# NNP-DWG-165-001-000_BP2_Analog-Digital_P.net
KiCad netlist of a schematic drawn in Altium Designer
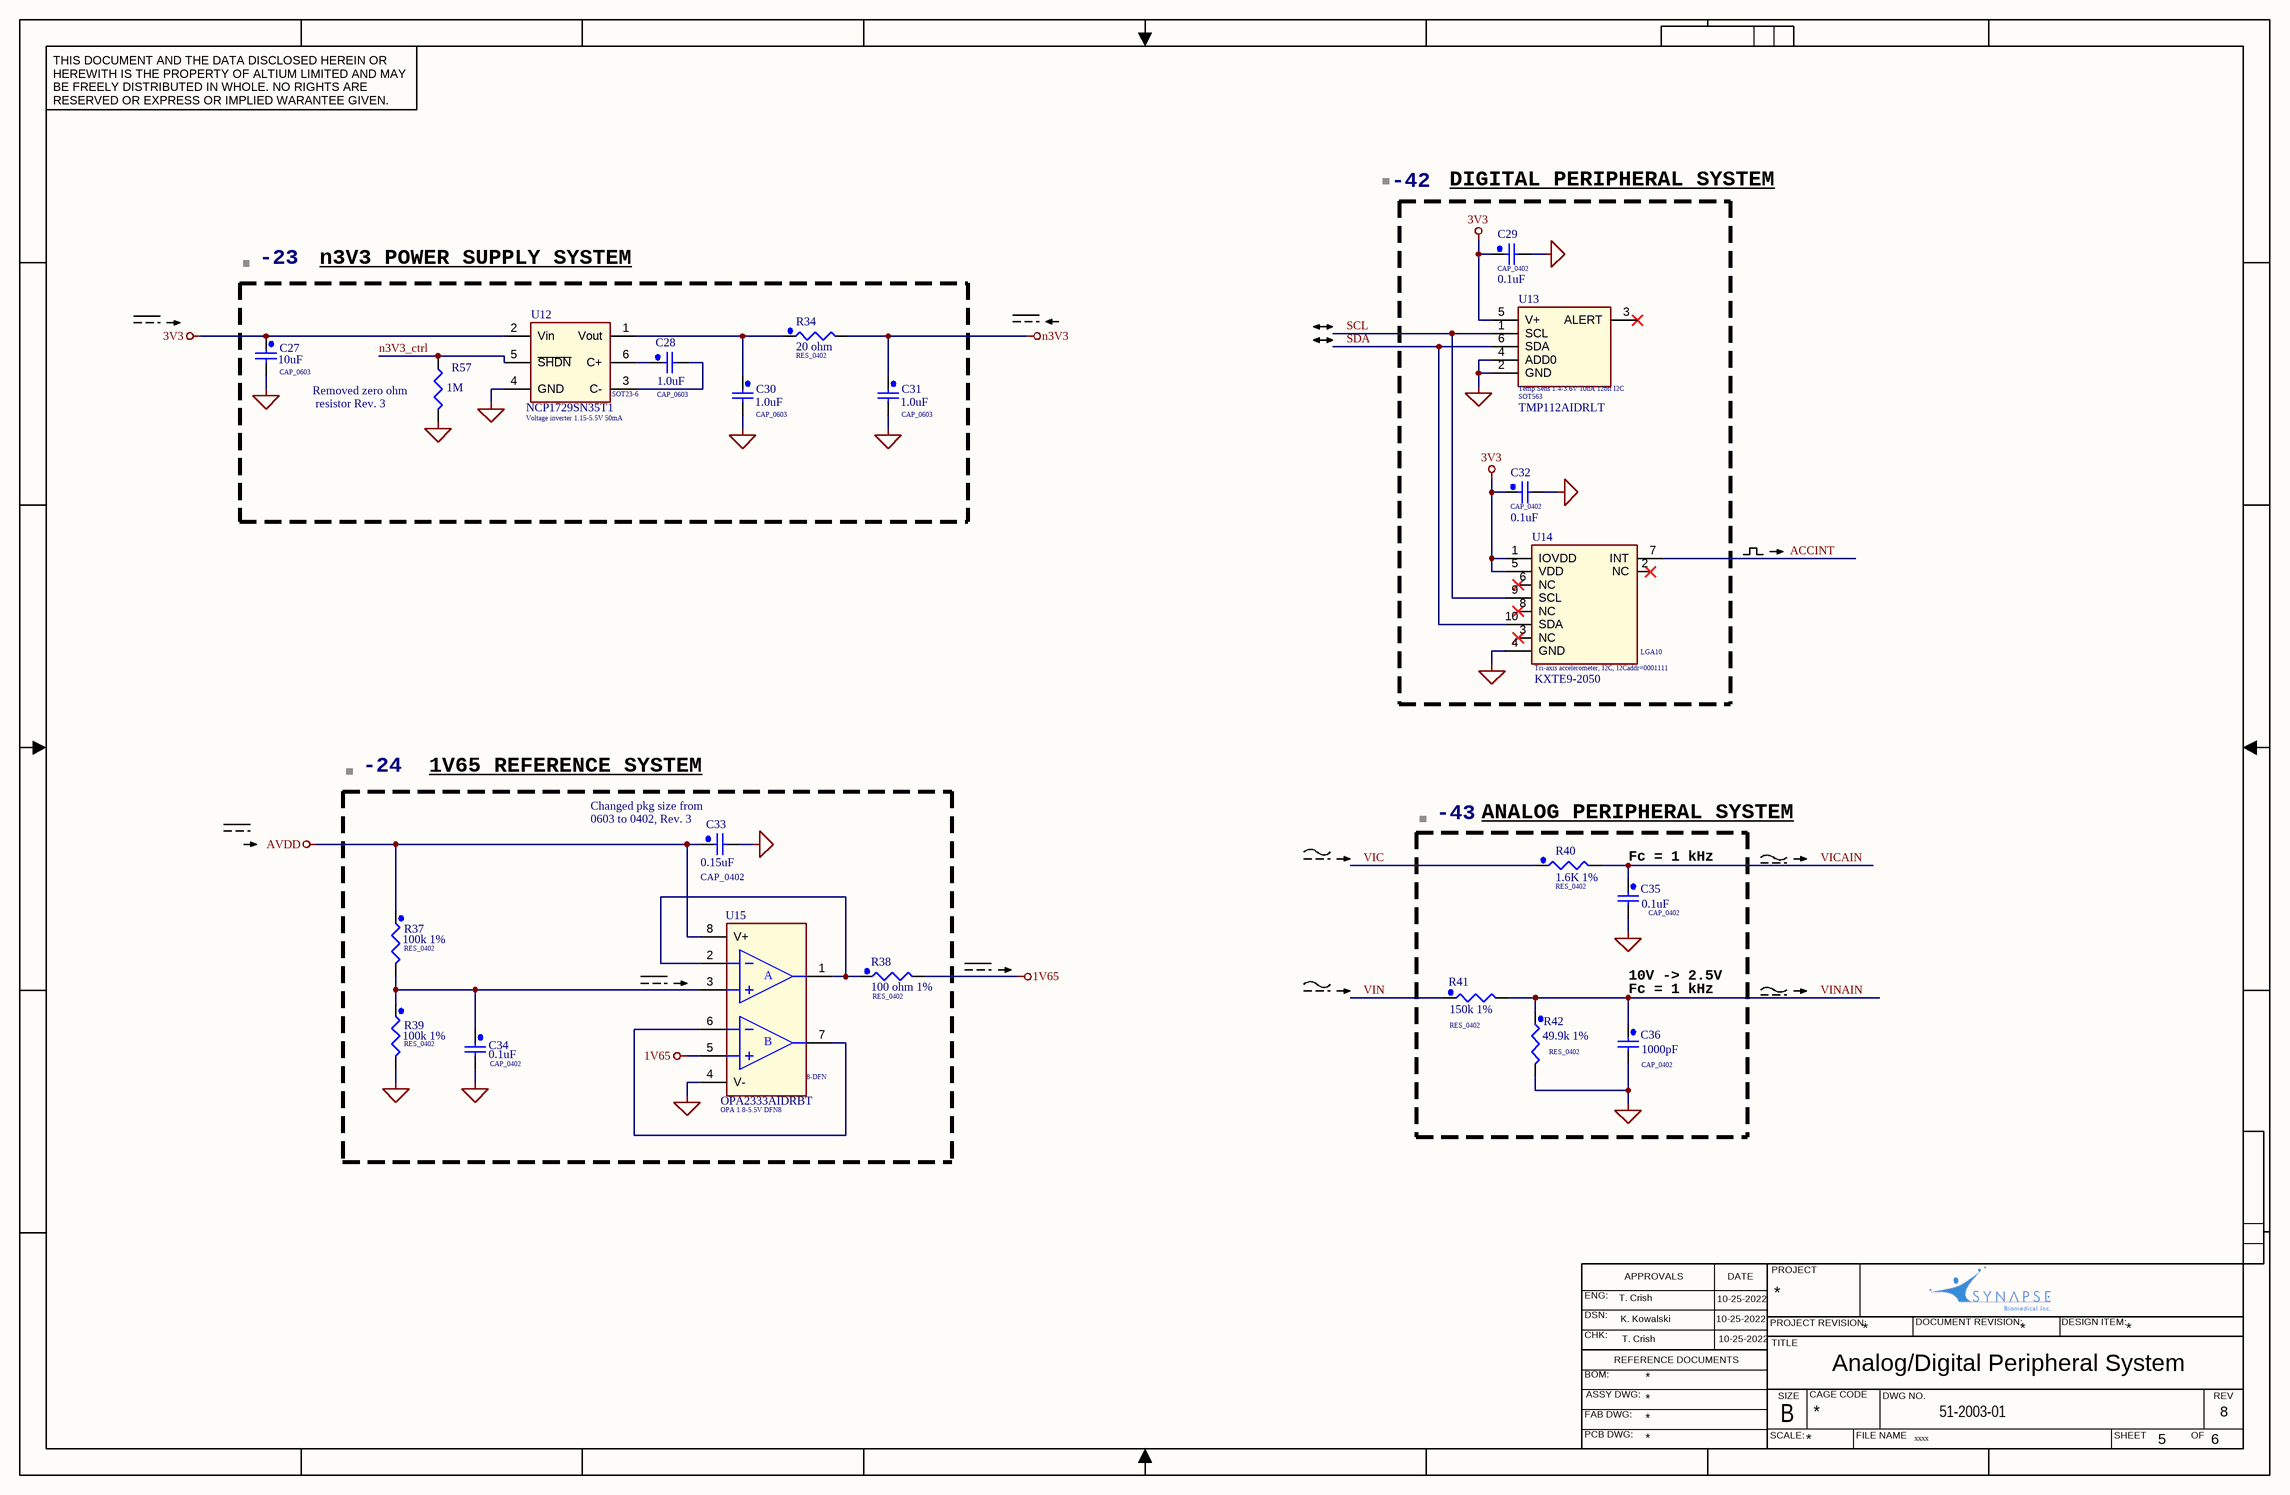
[diagram p0: NNP-DWG-165-001-000 BP2 Analog-Digital Peripheral System Pg 5 of 6.SchDoc]

(export (version "E")
  (design (tool "Eeschema 10.0.6"))
  (components
    (comp (ref "-23")
      (value "BOM_S1")
      (description "BOM item small graphic")
      (fields (field (name "XDESCRIPTION") "n3V3 POWER SUPPLY SYSTEM"))
      (libsource (lib "BOM_sym") (part "BOM_S1"))
    )
    (comp (ref "-24")
      (value "BOM_S1")
      (description "BOM item small graphic")
      (fields (field (name "XDESCRIPTION") "1V65 REFERENCE SYSTEM"))
      (libsource (lib "BOM_sym") (part "BOM_S1"))
    )
    (comp (ref "-42")
      (value "BOM_S1")
      (description "BOM item small graphic")
      (fields (field (name "XDESCRIPTION") "DIGITAL PERIPHERAL SYSTEM"))
      (libsource (lib "BOM_sym") (part "BOM_S1"))
    )
    (comp (ref "-43")
      (value "BOM_S1")
      (description "BOM item small graphic")
      (fields (field (name "XDESCRIPTION") "ANALOG PERIPHERAL SYSTEM"))
      (libsource (lib "BOM_sym") (part "BOM_S1"))
    )
    (comp (ref "C27")
      (value "10uF")
      (footprint "CAP_0603")
      (description "10uF, 6.3V, X5R, 0603_20%, RoHS")
      (fields
        (field (name "MFR") "Murata Electronics North America")
        (field (name "PACKAGEDESCRIPTION") "CAP_0603")
        (field (name "MPN") "GRM188R60J106ME47J")
      )
      (libsource (lib "NNPS Integrated Parts") (part "GRM188R60J106ME47J"))
    )
    (comp (ref "C28")
      (value "1.0uF")
      (footprint "CAP_0603")
      (description "1.0uF, 25V, X7R, 0603, 10%, RoHs")
      (fields
        (field (name "MFR") "TDK Corp")
        (field (name "PACKAGEDESCRIPTION") "CAP_0603")
        (field (name "MPN") "CGA3E1X7R1C105K080AC")
      )
      (libsource (lib "NNPS Integrated Parts") (part "GRM188R60J106ME47J"))
    )
    (comp (ref "C29")
      (value "0.1uF")
      (footprint "CAP_0402")
      (description "0.1uF, 16V, X7R, 0402, RoHS")
      (fields
        (field (name "MFR") "Murata Electronics North America")
        (field (name "PACKAGEDESCRIPTION") "CAP_0402")
        (field (name "MPN") "GRM155R71C104KA88D")
      )
      (libsource (lib "NNPS Integrated Parts") (part "GRM155R71C104KA88D"))
    )
    (comp (ref "C30")
      (value "1.0uF")
      (footprint "CAP_0603")
      (description "1.0uF, 25V, X7R, 0603, 10%, RoHs")
      (fields
        (field (name "MFR") "TDK Corp")
        (field (name "PACKAGEDESCRIPTION") "CAP_0603")
        (field (name "MPN") "CGA3E1X7R1C105K080AC")
      )
      (libsource (lib "NNPS Integrated Parts") (part "GRM188R60J106ME47J"))
    )
    (comp (ref "C31")
      (value "1.0uF")
      (footprint "CAP_0603")
      (description "1.0uF, 25V, X7R, 0603, 10%, RoHs")
      (fields
        (field (name "MFR") "TDK Corp")
        (field (name "PACKAGEDESCRIPTION") "CAP_0603")
        (field (name "MPN") "CGA3E1X7R1C105K080AC")
      )
      (libsource (lib "NNPS Integrated Parts") (part "GRM188R60J106ME47J"))
    )
    (comp (ref "C32")
      (value "0.1uF")
      (footprint "CAP_0402")
      (description "0.1uF, 16V, X7R, 0402, RoHS")
      (fields
        (field (name "MFR") "Murata Electronics North America")
        (field (name "PACKAGEDESCRIPTION") "CAP_0402")
        (field (name "MPN") "GRM155R71C104KA88D")
      )
      (libsource (lib "NNPS Integrated Parts") (part "GRM155R71C104KA88D"))
    )
    (comp (ref "C33")
      (value "0.15uF")
      (footprint "CAP_0402")
      (description "0.15uF, 16V, X7R, 10%, 0402, RoHS")
      (fields
        (field (name "MFR") "Murata Electronics North America")
        (field (name "PACKAGEDESCRIPTION") "CAP_0402")
        (field (name "MPN") "GRM155R71C154KA12D")
      )
      (libsource (lib "NNPS Integrated Parts") (part "GRM188R71C154KA01D"))
    )
    (comp (ref "C34")
      (value "0.1uF")
      (footprint "CAP_0402")
      (description "0.1uF, 16V, X7R, 0402, RoHS")
      (fields
        (field (name "MFR") "Murata Electronics North America")
        (field (name "PACKAGEDESCRIPTION") "CAP_0402")
        (field (name "MPN") "GRM155R71C104KA88D")
      )
      (libsource (lib "NNPS Integrated Parts") (part "GRM155R71C104KA88D"))
    )
    (comp (ref "C35")
      (value "0.1uF")
      (footprint "CAP_0402")
      (description "0.1uF, 16V, X7R, 0402, RoHS")
      (fields
        (field (name "MFR") "Murata Electronics North America")
        (field (name "PACKAGEDESCRIPTION") "CAP_0402")
        (field (name "MPN") "GRM155R71C104KA88D")
      )
      (libsource (lib "NNPS Integrated Parts") (part "GRM155R71C104KA88D"))
    )
    (comp (ref "C36")
      (value "1000pF")
      (footprint "CAP_0402")
      (description "1000pF, 50V, C0G, 5%, 0402, RoHS")
      (fields
        (field (name "MFR") "Murata Electronics North America")
        (field (name "PACKAGEDESCRIPTION") "CAP_0402")
        (field (name "MPN") "GRM1555C1H102JA01D")
      )
      (libsource (lib "NNPS Integrated Parts") (part "GRM1555C1H102JA01D"))
    )
    (comp (ref "R34")
      (value "20 ohm")
      (footprint "RES_0402")
      (description "20 ohm, 1%, 0402, 1%, RoHS")
      (fields
        (field (name "MFR") "Vishay")
        (field (name "PACKAGEDESCRIPTION") "RES_0402")
        (field (name "MPN") "CRCW040220R0FKED")
      )
      (libsource (lib "NNPS Integrated Parts") (part "CRCW040220R0FKED"))
    )
    (comp (ref "R37")
      (value "100k 1%")
      (footprint "RES_0402")
      (description "100k ohm, 1%, 1/16W, smd, 0402, RoHS")
      (fields
        (field (name "MFR") "Vishay Dale")
        (field (name "PACKAGEDESCRIPTION") "RES_0402")
        (field (name "MPN") "CRCW0402100KFKED")
      )
      (libsource (lib "NNPS Integrated Parts") (part "CRCW0402100KFKED"))
    )
    (comp (ref "R38")
      (value "100 ohm 1%")
      (footprint "RES_0402")
      (description "100 ohm, 1%, 1/16W, 0402, RoHS")
      (fields
        (field (name "MFR") "Vishay Dale")
        (field (name "PACKAGEDESCRIPTION") "RES_0402")
        (field (name "MPN") "CRCW0402100RFKED")
      )
      (libsource (lib "NNPS Integrated Parts") (part "CRCW0402100RFKED"))
    )
    (comp (ref "R39")
      (value "100k 1%")
      (footprint "RES_0402")
      (description "100k ohm, 1%, 1/16W, smd, 0402, RoHS")
      (fields
        (field (name "MFR") "Vishay Dale")
        (field (name "PACKAGEDESCRIPTION") "RES_0402")
        (field (name "MPN") "CRCW0402100KFKED")
      )
      (libsource (lib "NNPS Integrated Parts") (part "CRCW0402100KFKED"))
    )
    (comp (ref "R40")
      (value "1.6K 1%")
      (footprint "RES_0402")
      (description "1.6K ohm, 1%, 1/16W, smd, 0402, RoHS")
      (fields
        (field (name "MFR") "Vishay Dale")
        (field (name "PACKAGEDESCRIPTION") "RES_0402")
        (field (name "MPN") "CRCW04021K60FKED")
      )
      (libsource (lib "NNPS Integrated Parts") (part "CRCW04021K60FKED"))
    )
    (comp (ref "R41")
      (value "150k 1%")
      (footprint "RES_0402")
      (description "150k ohm, 1%, 1/16W, smd, 0402, RoHS")
      (fields
        (field (name "MFR") "Vishay Dale")
        (field (name "PACKAGEDESCRIPTION") "RES_0402")
        (field (name "MPN") "CRCW0402150KFKED")
      )
      (libsource (lib "NNPS Integrated Parts") (part "CRCW0402150KFKED"))
    )
    (comp (ref "R42")
      (value "49.9k 1%")
      (footprint "RES_0402")
      (description "49.9k ohm, 1%, 1/16W, 0402, RoHS")
      (fields
        (field (name "MFR") "Vishay Dale")
        (field (name "PACKAGEDESCRIPTION") "RES_0402")
        (field (name "MPN") "CRCW040249K9FKED")
      )
      (libsource (lib "NNPS Integrated Parts") (part "MCR01MZPF4992"))
    )
    (comp (ref "R57")
      (value "1M")
      (footprint "CHIP_0402N")
      (description "Resistor 1M 0402 1% 63mW")
      (fields (field (name "MANUFACTURER") "Rohm") (field (name "Comment") "1M 0402 Resistor"))
      (libsource (lib "NNPS Integrated Parts1") (part "R_1M_0402"))
    )
    (comp (ref "U12")
      (value "Voltage inverter 1.15-5.5V 50mA")
      (footprint "SOT23-6")
      (description "Voltage inverter, 1.15-5.5V, 50mA, SOT23-6, RoHS")
      (fields
        (field (name "MFR") "ON Semiconductor")
        (field (name "PACKAGEDESCRIPTION") "SOT23-6")
        (field (name "MPN") "NCP1729SN35T1")
      )
      (libsource (lib "NNPS Integrated Parts") (part "NCP1729SN35T1"))
    )
    (comp (ref "U13")
      (value "Temp Sens 1.4-3.6V 10uA 12bit I2C")
      (footprint "SOT-563")
      (description "Temperature Sensor,12bit I2C,  SOT563, RoHS")
      (fields
        (field (name "MFR") "Texas Instruments")
        (field (name "PACKAGEDESCRIPTION") "SOT563")
        (field (name "MPN") "TMP112AIDRLT")
      )
      (libsource (lib "NNPS Integrated Parts") (part "TMP112AIDRLT"))
    )
    (comp (ref "U14")
      (value "Tri-axis accelerometer, I2C, I2Caddr=0001111")
      (footprint "LGA10")
      (description "Tri-axis accelerometer, I2C,  LGA10, RoHS")
      (fields
        (field (name "MFR") "Kionix")
        (field (name "PACKAGEDESCRIPTION") "LGA10")
        (field (name "MPN") "KXTE9-2050")
      )
      (libsource (lib "NNPS Integrated Parts") (part "KXTE9-2050"))
    )
    (comp (ref "U15")
      (value "OPA 1.8-5.5V DFN8")
      (footprint "TI-DRB8-2400X1650TP_V")
      (description "OPA, 1.8-5.5V, DFN8, RoHS")
      (fields
        (field (name "PACKAGEDESCRIPTION") "8-DFN")
        (field (name "MFR") "Texas Instruments")
        (field (name "MPN") "OPA2333AIDRBT")
      )
      (libsource (lib "NNPS Integrated Parts") (part "OPA2333AIDRBT"))
    )
  )
  (nets
    (net (code "1") (name "/ACCINT") (class "Default")
      (node (ref "U14") (pin "7") (pinfunction "INT_7") (pintype "passive"))
    )
    (net (code "2") (name "/SCL") (class "Default")
      (node (ref "U13") (pin "1") (pinfunction "SCL_1") (pintype "passive"))
      (node (ref "U14") (pin "9") (pinfunction "SCL_9") (pintype "passive"))
    )
    (net (code "3") (name "/SDA") (class "Default")
      (node (ref "U13") (pin "6") (pinfunction "SDA_6") (pintype "passive"))
      (node (ref "U14") (pin "10") (pinfunction "SDA_10") (pintype "passive"))
    )
    (net (code "4") (name "/VIC") (class "Default")
      (node (ref "R40") (pin "1") (pinfunction "1_1") (pintype "passive"))
    )
    (net (code "5") (name "/VICAIN") (class "Default")
      (node (ref "C35") (pin "1") (pinfunction "1_1") (pintype "passive"))
      (node (ref "R40") (pin "2") (pinfunction "2_2") (pintype "passive"))
    )
    (net (code "6") (name "/VIN") (class "Default")
      (node (ref "R41") (pin "1") (pinfunction "1_1") (pintype "passive"))
    )
    (net (code "7") (name "/VINAIN") (class "Default")
      (node (ref "C36") (pin "1") (pinfunction "1_1") (pintype "passive"))
      (node (ref "R41") (pin "2") (pinfunction "2_2") (pintype "passive"))
      (node (ref "R42") (pin "1") (pinfunction "1_1") (pintype "passive"))
    )
    (net (code "8") (name "/n3V3_ctrl") (class "Default")
      (node (ref "R57") (pin "1") (pinfunction "1_1") (pintype "passive"))
      (node (ref "U12") (pin "5") (pinfunction "SHDN_5") (pintype "passive"))
    )
    (net (code "9") (name "1V65") (class "Default")
      (node (ref "R38") (pin "2") (pinfunction "2_2") (pintype "passive"))
      (node (ref "U15") (pin "5") (pinfunction "+IN_B_5") (pintype "passive"))
    )
    (net (code "10") (name "3V3") (class "Default")
      (node (ref "C27") (pin "1") (pinfunction "1_1") (pintype "passive"))
      (node (ref "C29") (pin "1") (pinfunction "1_1") (pintype "passive"))
      (node (ref "C32") (pin "1") (pinfunction "1_1") (pintype "passive"))
      (node (ref "U12") (pin "2") (pinfunction "Vin_2") (pintype "passive"))
      (node (ref "U13") (pin "5") (pinfunction "V+_5") (pintype "power_in"))
      (node (ref "U14") (pin "1") (pinfunction "IOVDD_1") (pintype "passive"))
      (node (ref "U14") (pin "5") (pinfunction "VDD_5") (pintype "passive"))
    )
    (net (code "11") (name "AVDD") (class "Default")
      (node (ref "C33") (pin "1") (pinfunction "1_1") (pintype "passive"))
      (node (ref "R37") (pin "1") (pinfunction "1_1") (pintype "passive"))
      (node (ref "U15") (pin "8") (pinfunction "V+_8") (pintype "passive"))
    )
    (net (code "12") (name "GND") (class "Default")
      (node (ref "C27") (pin "2") (pinfunction "2_2") (pintype "passive"))
      (node (ref "C29") (pin "2") (pinfunction "2_2") (pintype "passive"))
      (node (ref "C30") (pin "2") (pinfunction "2_2") (pintype "passive"))
      (node (ref "C31") (pin "2") (pinfunction "2_2") (pintype "passive"))
      (node (ref "C32") (pin "2") (pinfunction "2_2") (pintype "passive"))
      (node (ref "C33") (pin "2") (pinfunction "2_2") (pintype "passive"))
      (node (ref "C34") (pin "2") (pinfunction "2_2") (pintype "passive"))
      (node (ref "C35") (pin "2") (pinfunction "2_2") (pintype "passive"))
      (node (ref "C36") (pin "2") (pinfunction "2_2") (pintype "passive"))
      (node (ref "R39") (pin "2") (pinfunction "2_2") (pintype "passive"))
      (node (ref "R42") (pin "2") (pinfunction "2_2") (pintype "passive"))
      (node (ref "R57") (pin "2") (pinfunction "2_2") (pintype "passive"))
      (node (ref "U12") (pin "4") (pinfunction "GND_4") (pintype "passive"))
      (node (ref "U13") (pin "2") (pinfunction "GND_2") (pintype "power_in"))
      (node (ref "U13") (pin "4") (pinfunction "ADD0_4") (pintype "passive"))
      (node (ref "U14") (pin "4") (pinfunction "GND_4") (pintype "passive"))
      (node (ref "U15") (pin "4") (pinfunction "V-_4") (pintype "passive"))
    )
    (net (code "13") (name "Net-(U12-C+)") (class "Default")
      (node (ref "C28") (pin "1") (pinfunction "1_1") (pintype "passive"))
      (node (ref "U12") (pin "6") (pinfunction "C+_6") (pintype "passive"))
    )
    (net (code "14") (name "Net-(U12-C-)") (class "Default")
      (node (ref "C28") (pin "2") (pinfunction "2_2") (pintype "passive"))
      (node (ref "U12") (pin "3") (pinfunction "C-_3") (pintype "passive"))
    )
    (net (code "15") (name "Net-(U12-Vout)") (class "Default")
      (node (ref "C30") (pin "1") (pinfunction "1_1") (pintype "passive"))
      (node (ref "R34") (pin "1") (pinfunction "1_1") (pintype "passive"))
      (node (ref "U12") (pin "1") (pinfunction "Vout_1") (pintype "passive"))
    )
    (net (code "16") (name "Net-(U15-+IN_A)") (class "Default")
      (node (ref "C34") (pin "1") (pinfunction "1_1") (pintype "passive"))
      (node (ref "R37") (pin "2") (pinfunction "2_2") (pintype "passive"))
      (node (ref "R39") (pin "1") (pinfunction "1_1") (pintype "passive"))
      (node (ref "U15") (pin "3") (pinfunction "+IN_A_3") (pintype "passive"))
    )
    (net (code "17") (name "Net-(U15--IN_A)") (class "Default")
      (node (ref "R38") (pin "1") (pinfunction "1_1") (pintype "passive"))
      (node (ref "U15") (pin "1") (pinfunction "OUT_A_1") (pintype "passive"))
      (node (ref "U15") (pin "2") (pinfunction "-IN_A_2") (pintype "passive"))
    )
    (net (code "18") (name "Net-(U15--IN_B)") (class "Default")
      (node (ref "U15") (pin "6") (pinfunction "-IN_B_6") (pintype "passive"))
      (node (ref "U15") (pin "7") (pinfunction "OUT_B_7") (pintype "passive"))
    )
    (net (code "19") (name "n3V3") (class "Default")
      (node (ref "C31") (pin "1") (pinfunction "1_1") (pintype "passive"))
      (node (ref "R34") (pin "2") (pinfunction "2_2") (pintype "passive"))
    )
    (net (code "20") (name "unconnected-(U13-ALERT-Pad3)") (class "Default")
      (node (ref "U13") (pin "3") (pinfunction "ALERT_3") (pintype "passive+no_connect"))
    )
    (net (code "21") (name "unconnected-(U14-NC-Pad2)") (class "Default")
      (node (ref "U14") (pin "2") (pinfunction "NC_2") (pintype "power_in+no_connect"))
    )
    (net (code "22") (name "unconnected-(U14-NC-Pad3)") (class "Default")
      (node (ref "U14") (pin "3") (pinfunction "NC_3") (pintype "passive+no_connect"))
    )
    (net (code "23") (name "unconnected-(U14-NC-Pad6)") (class "Default")
      (node (ref "U14") (pin "6") (pinfunction "NC_6") (pintype "passive+no_connect"))
    )
    (net (code "24") (name "unconnected-(U14-NC-Pad8)") (class "Default")
      (node (ref "U14") (pin "8") (pinfunction "NC_8") (pintype "passive+no_connect"))
    )
  )
)
